# v5_3.net
KiCad netlist of a schematic drawn in EAGLE
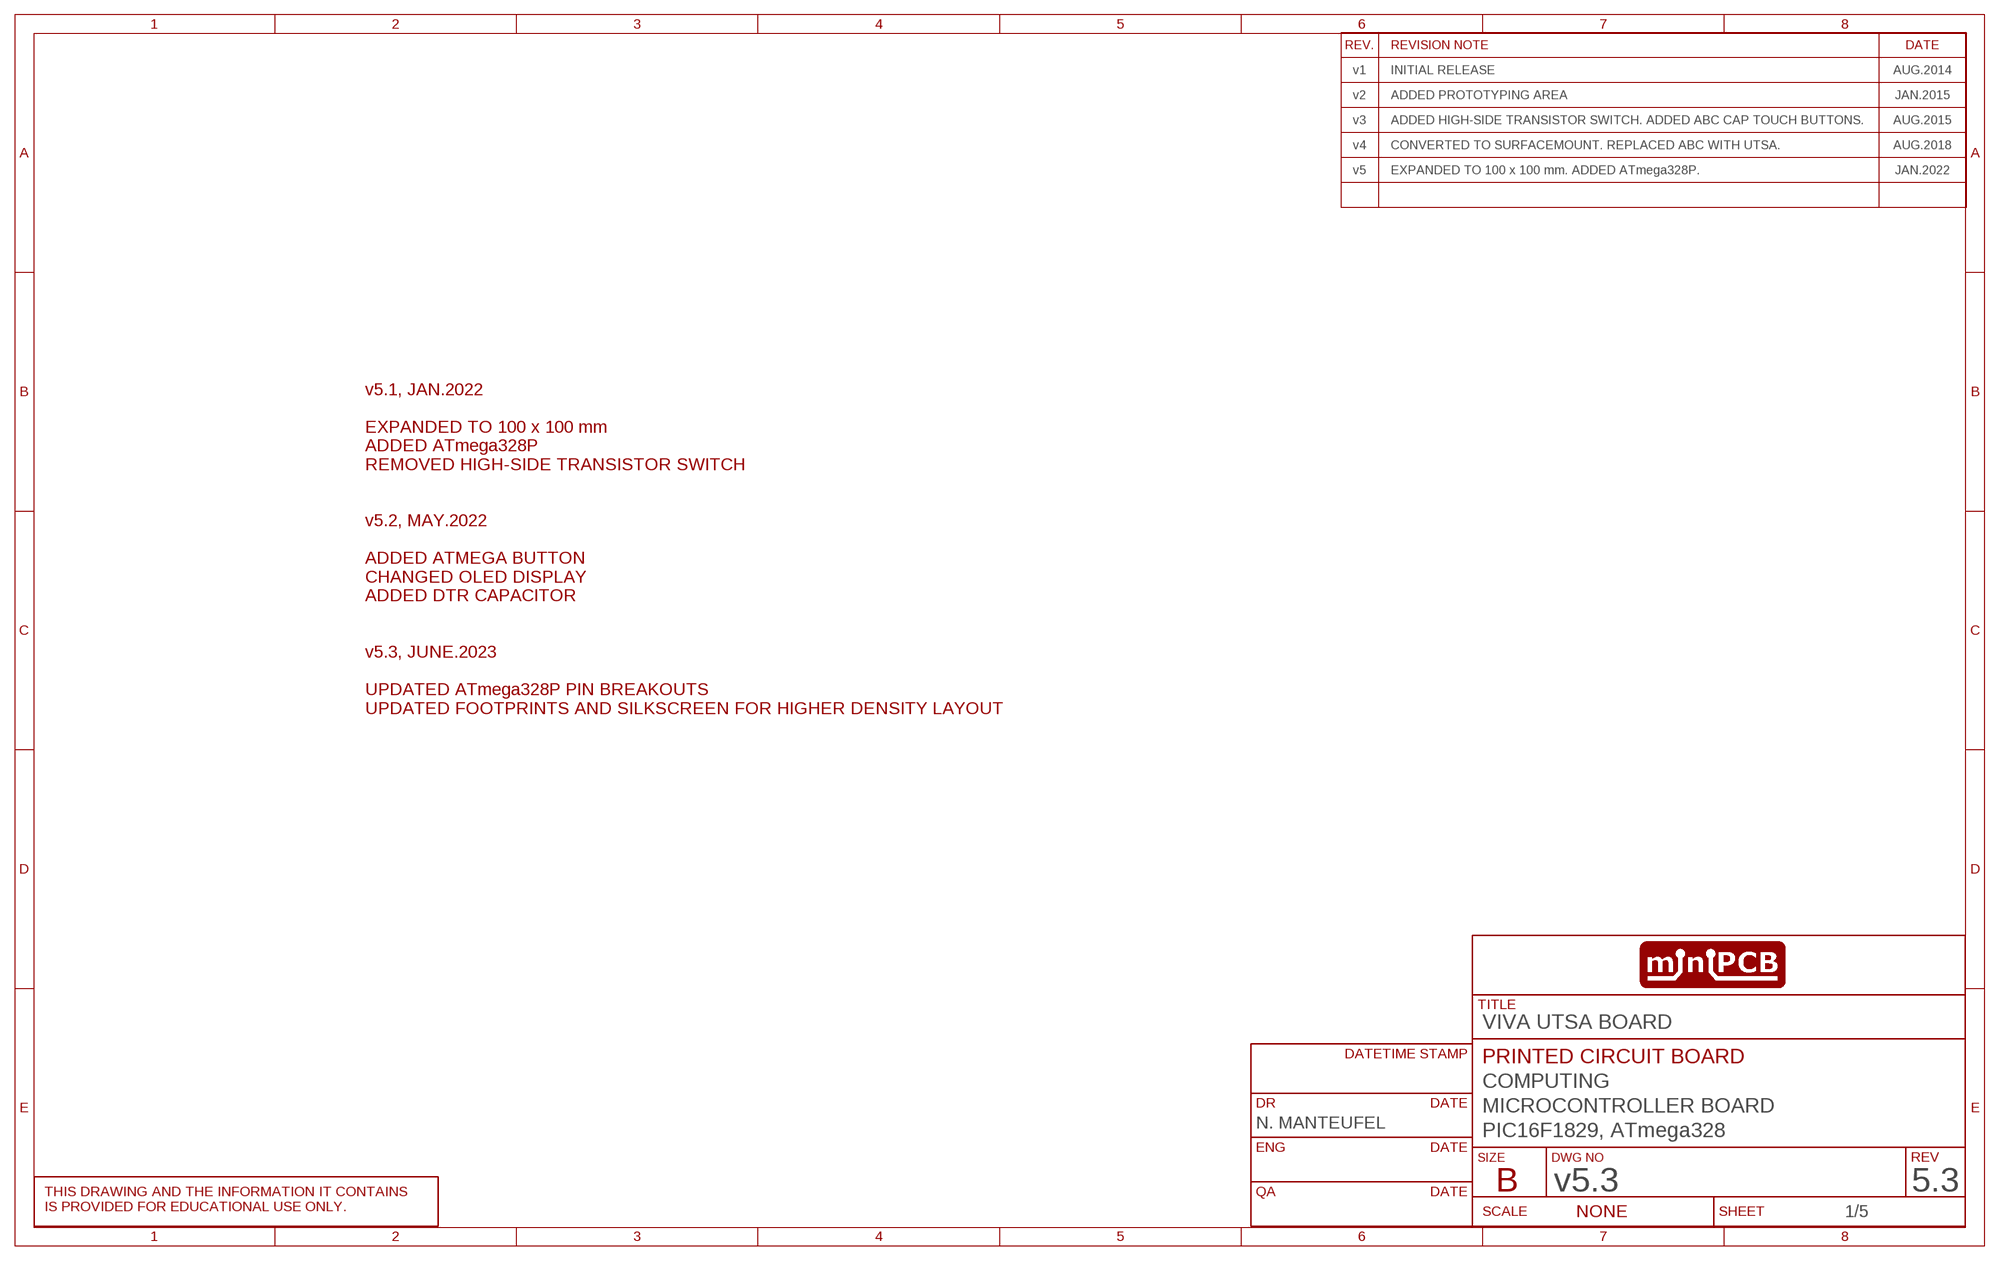
[diagram p0: schematic, sheet 1]
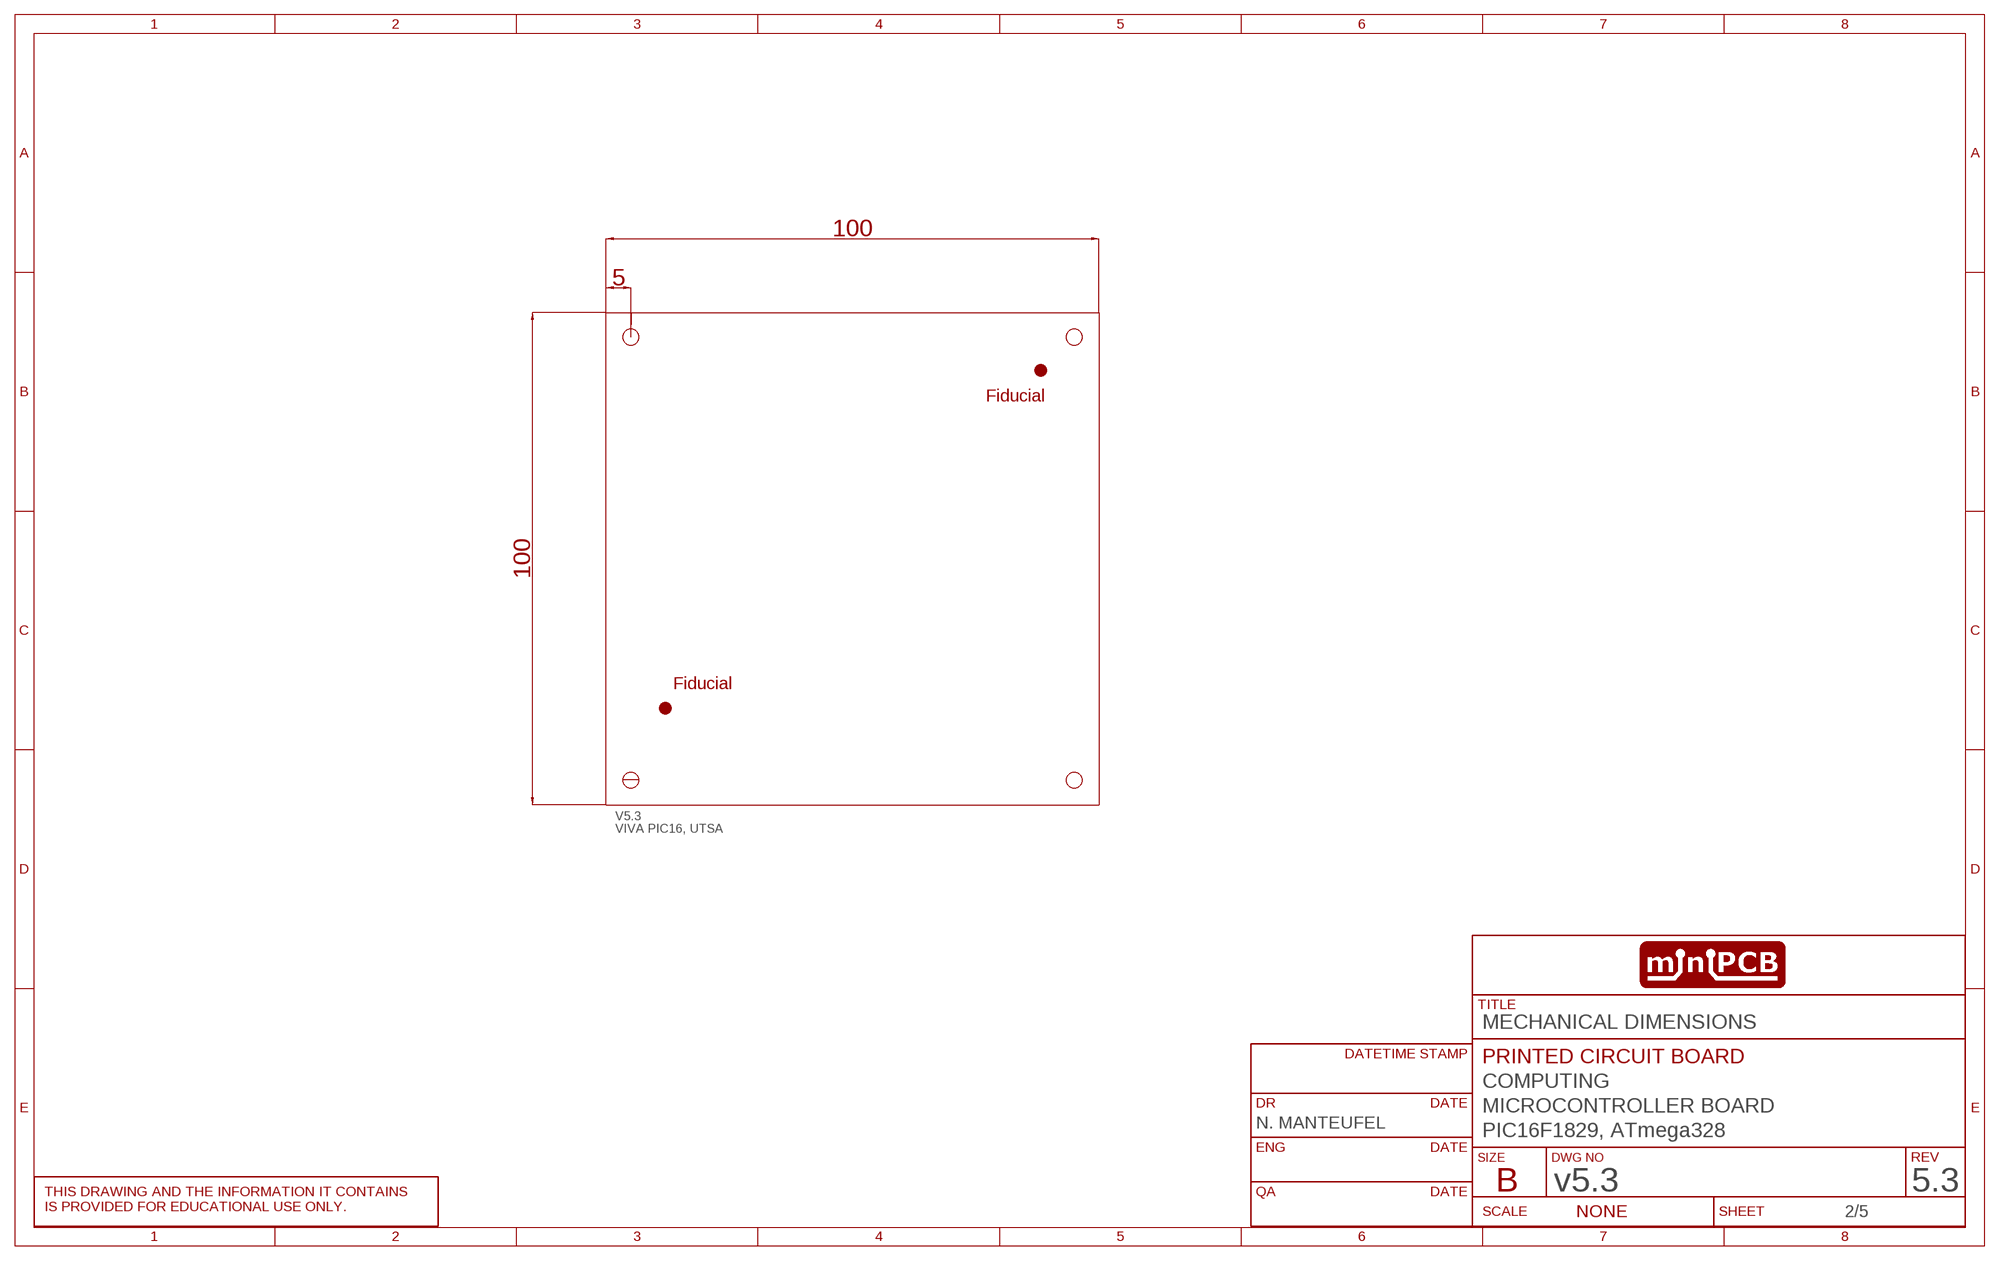
[diagram p1: schematic, sheet 2]
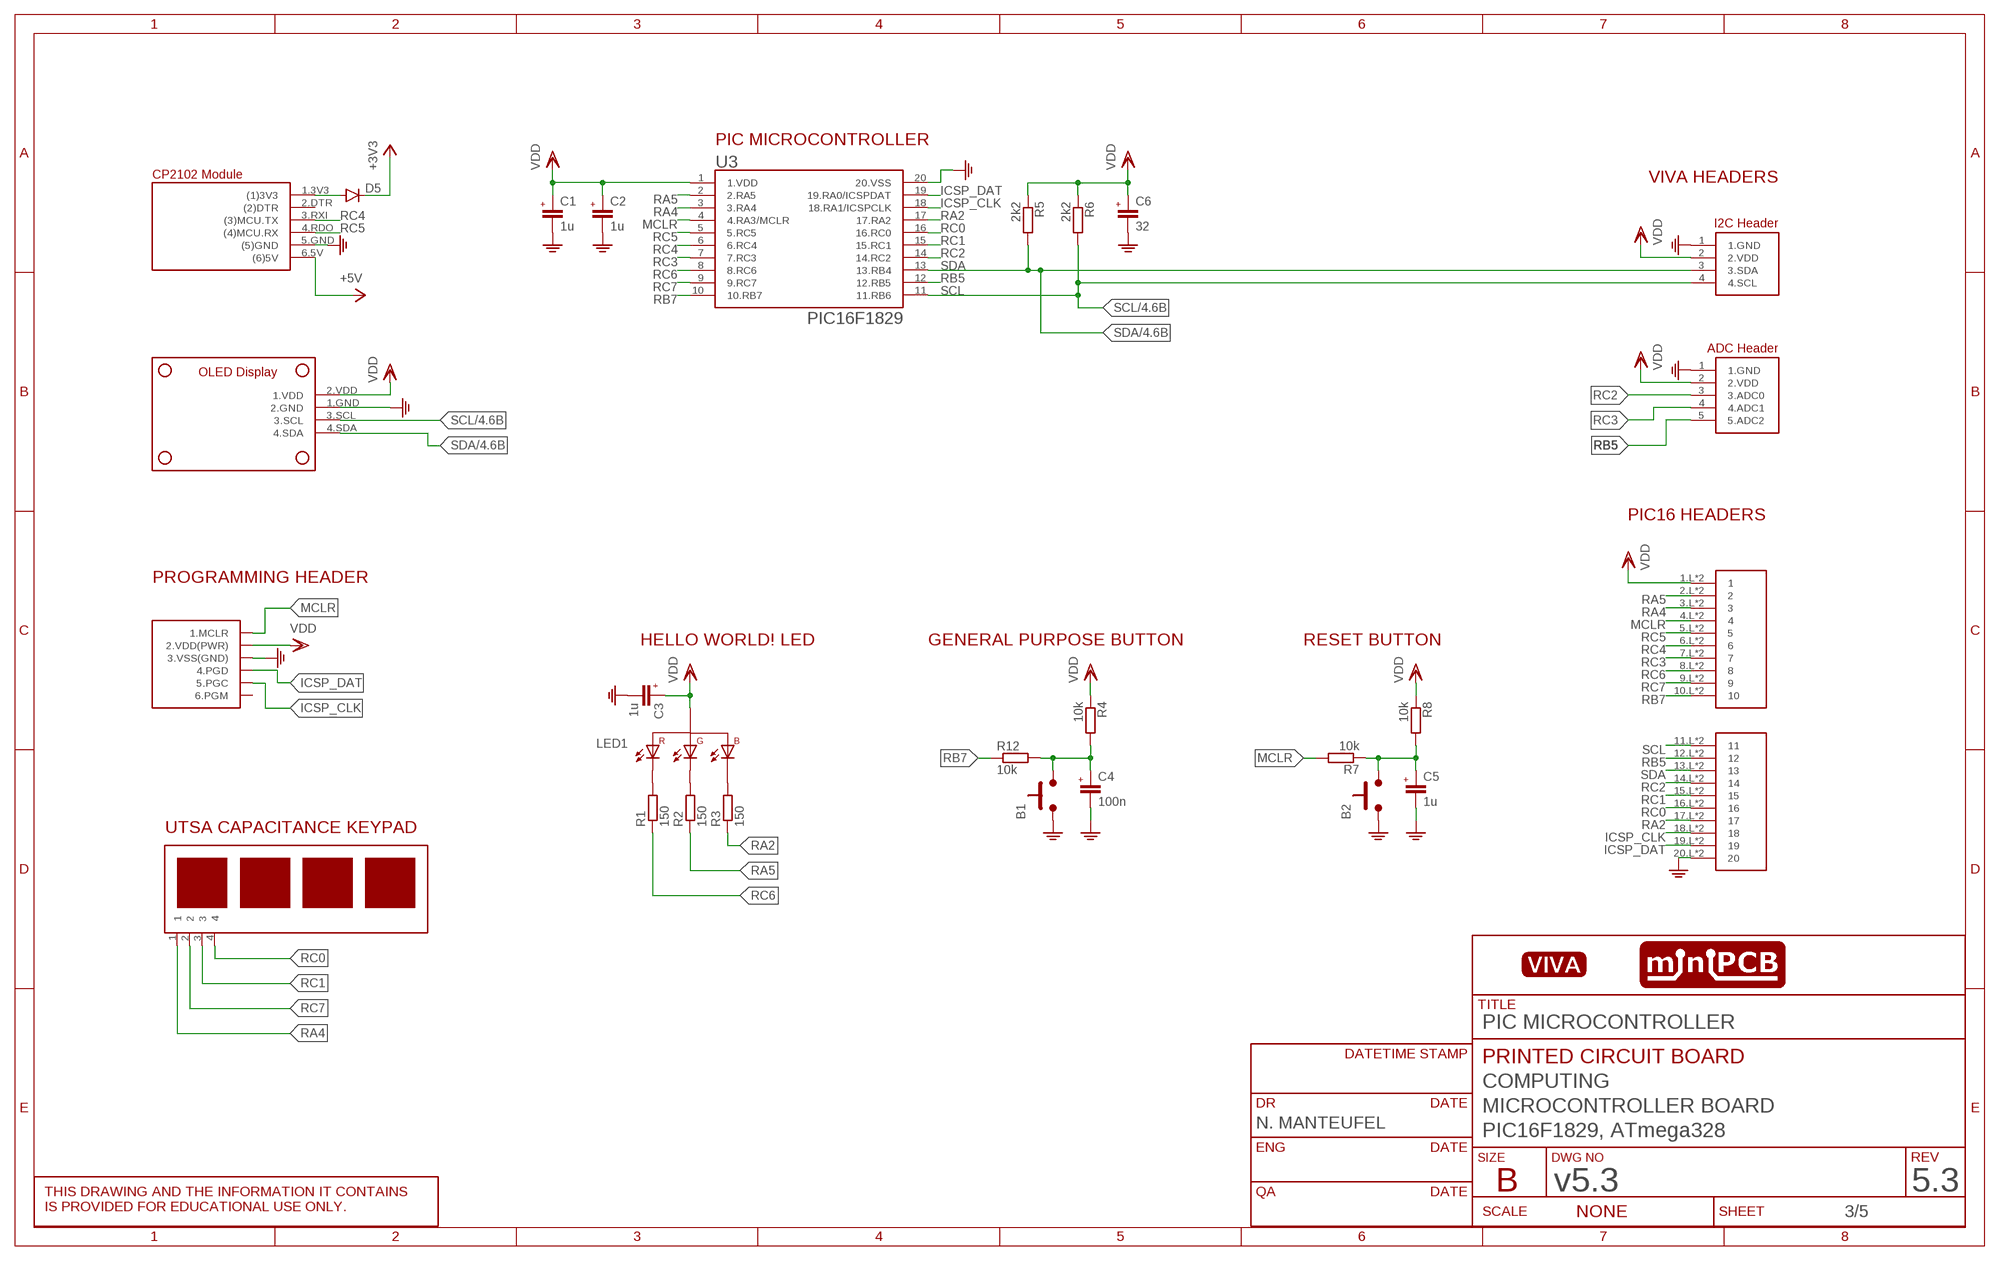
[diagram p2: schematic, sheet 3]
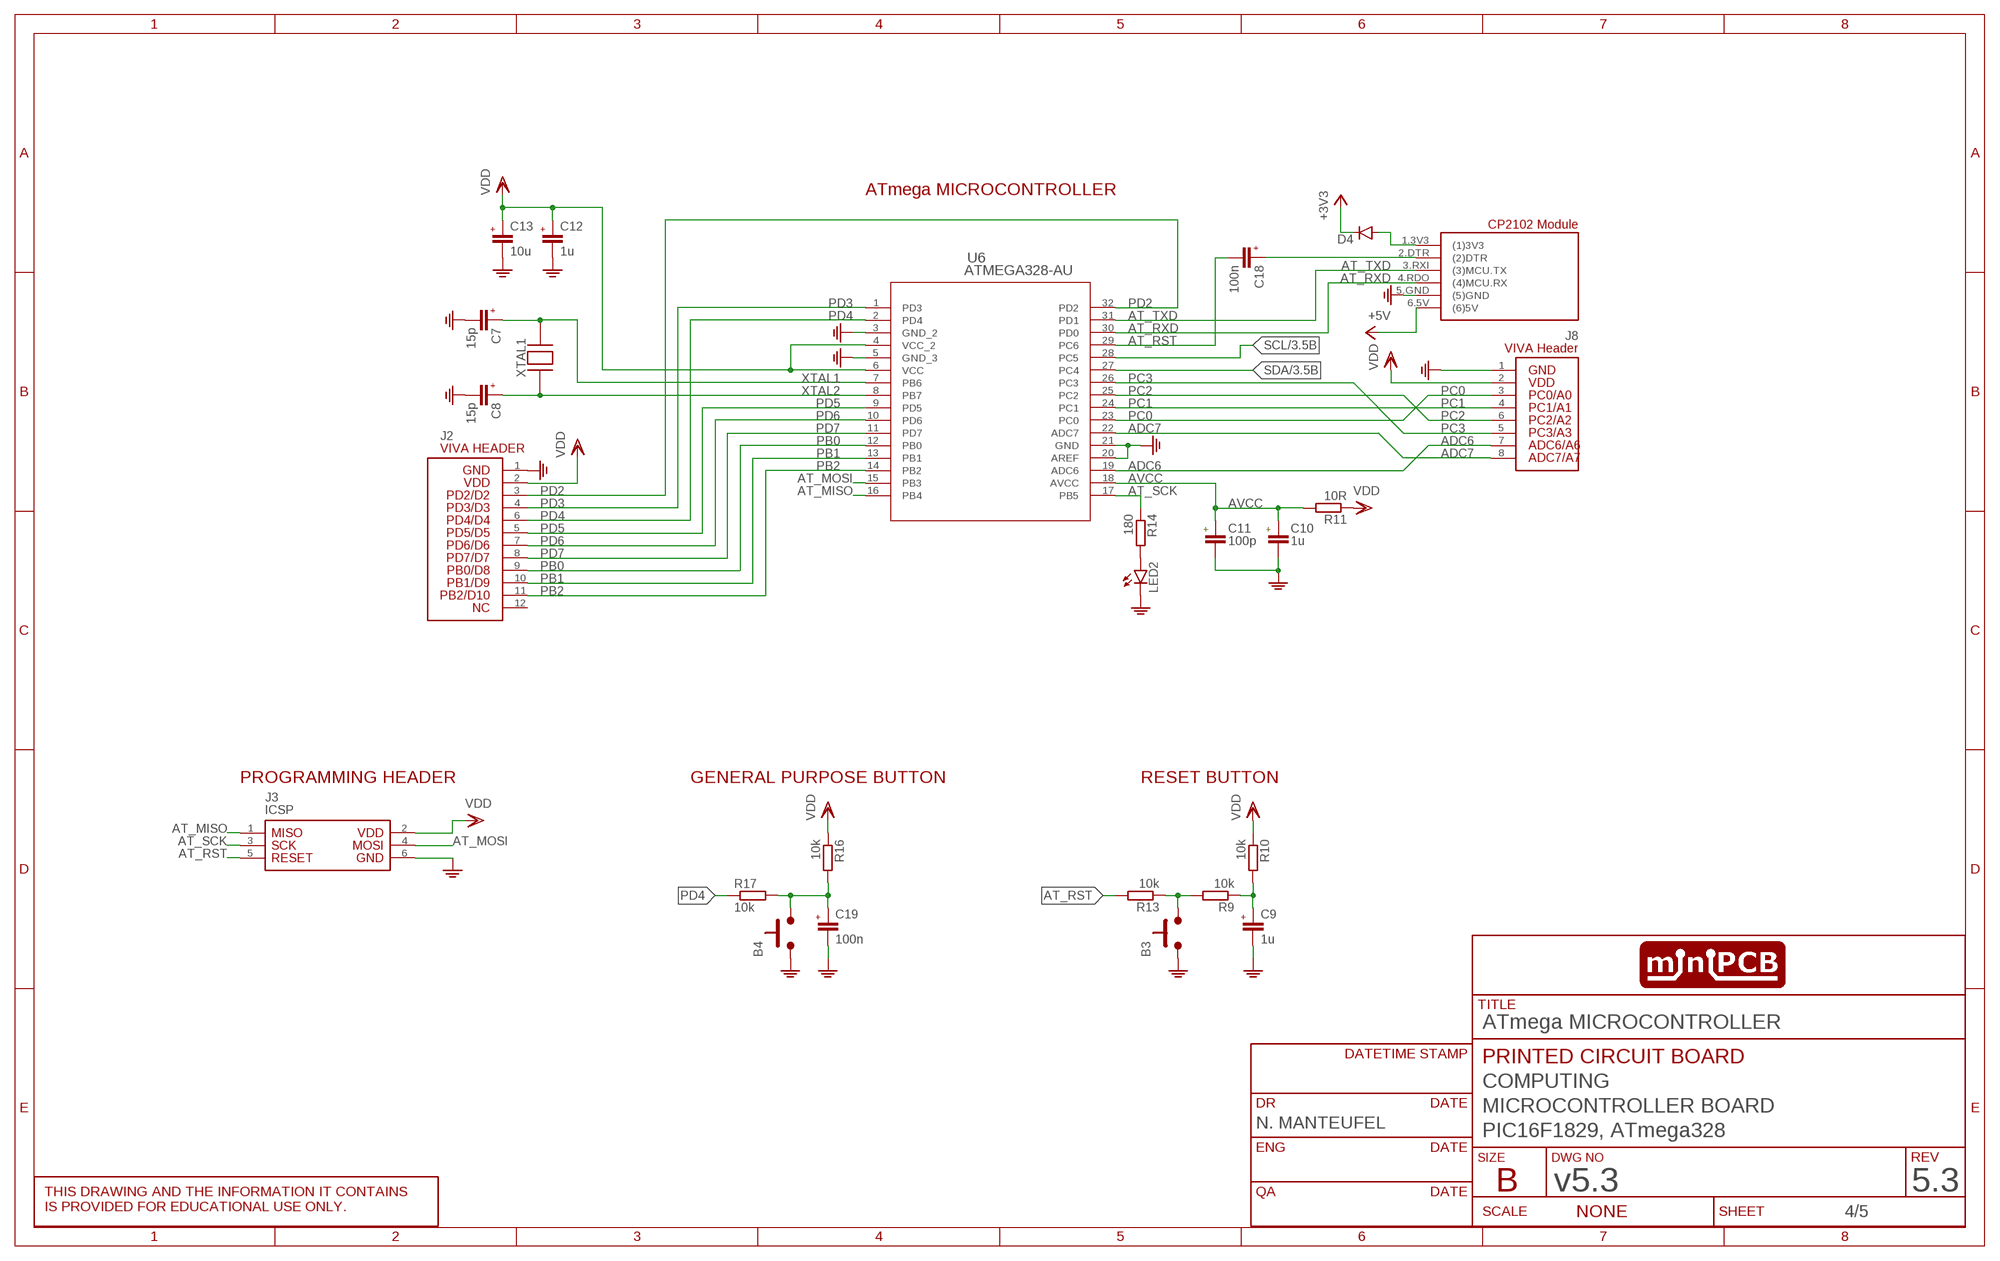
[diagram p3: schematic, sheet 4]
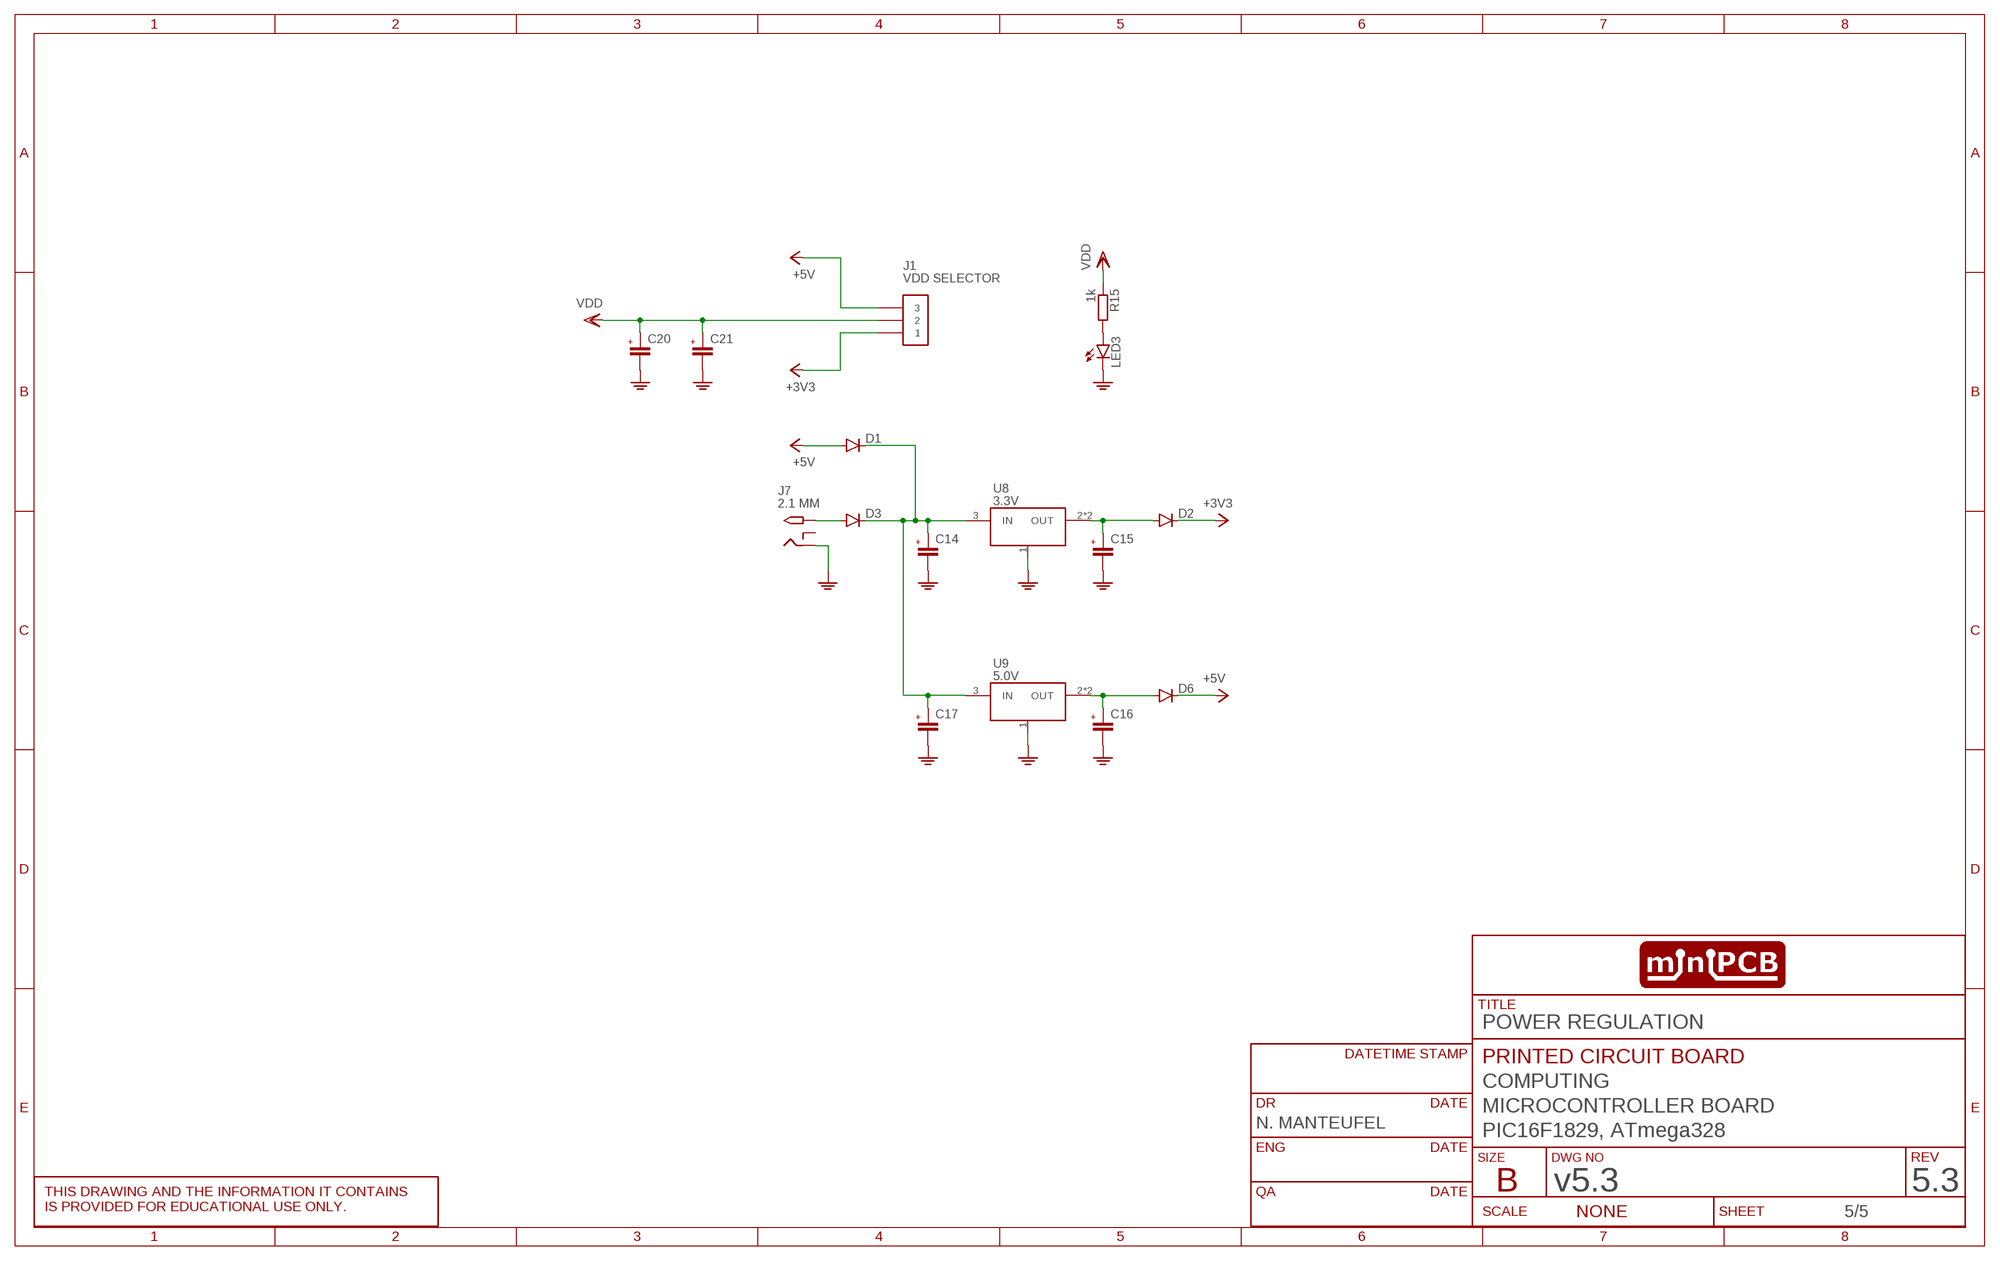
[diagram p4: schematic, sheet 5]

(export (version "E")
  (design (tool "Eeschema 10.0.6"))
  (components
    (comp (ref "A1")
      (value "FIDUCIAL")
      (footprint "eagle-import:FIDUCIAL")
      (libsource (lib "eagle-import") (part "FIDUCIAL"))
    )
    (comp (ref "A2")
      (value "FIDUCIAL")
      (footprint "eagle-import:FIDUCIAL")
      (libsource (lib "eagle-import") (part "FIDUCIAL"))
    )
    (comp (ref "V5.3")
      (value "VIVA PIC16, UTSA")
      (footprint "eagle-import:PCB_100X100")
      (libsource (lib "eagle-import") (part "PCB_100X100"))
    )
    (comp (ref "B3")
      (value "PUSHBUTTON6X6MM")
      (footprint "eagle-import:6X6MM")
      (libsource (lib "eagle-import") (part "PUSHBUTTON6X6MM"))
    )
    (comp (ref "B4")
      (value "PUSHBUTTON6X6MM")
      (footprint "eagle-import:6X6MM")
      (libsource (lib "eagle-import") (part "PUSHBUTTON6X6MM"))
    )
    (comp (ref "C7")
      (value "15p")
      (footprint "eagle-import:C0603")
      (libsource (lib "eagle-import") (part "C0603"))
    )
    (comp (ref "C8")
      (value "15p")
      (footprint "eagle-import:C0603")
      (libsource (lib "eagle-import") (part "C0603"))
    )
    (comp (ref "C9")
      (value "1u")
      (footprint "eagle-import:C0805")
      (libsource (lib "eagle-import") (part "C0805"))
    )
    (comp (ref "C10")
      (value "1u")
      (footprint "eagle-import:C0805")
      (libsource (lib "eagle-import") (part "C-EU_C0805"))
    )
    (comp (ref "C11")
      (value "100p")
      (footprint "eagle-import:C0805")
      (libsource (lib "eagle-import") (part "C-EU_C0805"))
    )
    (comp (ref "C12")
      (value "1u")
      (footprint "eagle-import:C0805")
      (libsource (lib "eagle-import") (part "C0805"))
    )
    (comp (ref "C13")
      (value "10u")
      (footprint "eagle-import:C0805")
      (libsource (lib "eagle-import") (part "C0805"))
    )
    (comp (ref "C18")
      (value "100n")
      (footprint "eagle-import:C0805")
      (libsource (lib "eagle-import") (part "C0805"))
    )
    (comp (ref "C19")
      (value "100n")
      (footprint "eagle-import:C0805")
      (libsource (lib "eagle-import") (part "C0805"))
    )
    (comp (ref "D4")
      (value "DIODE-DO214AC")
      (footprint "eagle-import:DO214AC")
      (libsource (lib "eagle-import") (part "DIODE-DO214AC"))
    )
    (comp (ref "J2")
      (value "VIVA-HEADER-12P")
      (footprint "eagle-import:VIVA-HEADER-12P")
      (fields
        (field (name "P3") "P3 TEXT")
        (field (name "P4") "P4 TEXT")
        (field (name "P5") "P5 TEXT")
        (field (name "P6") "P6 TEXT")
        (field (name "P7") "P7 TEXT")
        (field (name "P8") "P8 TEXT")
        (field (name "P9") "P9 TEXT")
        (field (name "P10") "P10 TEXT")
        (field (name "P11") "P11 TEXT")
        (field (name "P12") "P12 TEXT")
        (field (name "P10_1") "PB1/D9")
        (field (name "P11_1") "PB2/D10")
        (field (name "P12_1") "NC")
        (field (name "P3_1") "PD2/D2")
        (field (name "P4_1") "PD3/D3")
        (field (name "P5_1") "PD4/D4")
        (field (name "P6_1") "PD5/D5")
        (field (name "P7_1") "PD6/D6")
        (field (name "P8_1") "PD7/D7")
        (field (name "P9_1") "PB0/D8")
      )
      (libsource (lib "eagle-import") (part "VIVA-HEADER-12P"))
    )
    (comp (ref "J3")
      (value "ICSP")
      (footprint "eagle-import:PINS_6-2X3_AT")
      (fields
        (field (name "P1") "P1 NAME")
        (field (name "P3") "P3 NAME")
        (field (name "P5") "P5 NAME")
        (field (name "P2") "P2 NAME")
        (field (name "P4") "P4 NAME")
        (field (name "P6") "P6 NAME")
        (field (name "P1_1") "MISO")
        (field (name "P2_1") "VDD")
        (field (name "P3_1") "SCK")
        (field (name "P4_1") "MOSI")
        (field (name "P5_1") "RESET")
        (field (name "P6_1") "GND")
      )
      (libsource (lib "eagle-import") (part "PINS_6-2X3_AT"))
    )
    (comp (ref "J8")
      (value "VIVA-HEADER-ADC-8P")
      (footprint "eagle-import:VIVA-HEADER-ADC-8P")
      (fields
        (field (name "P3") "P3 TEXT")
        (field (name "P4") "P4 TEXT")
        (field (name "P5") "P5 TEXT")
        (field (name "P6") "P6 TEXT")
        (field (name "P7") "P7 TEXT")
        (field (name "P8") "P8 TEXT")
        (field (name "P3_1") "PC0/A0")
        (field (name "P4_1") "PC1/A1")
        (field (name "P5_1") "PC2/A2")
        (field (name "P6_1") "PC3/A3")
        (field (name "P7_1") "ADC6/A6")
        (field (name "P8_1") "ADC7/A7")
      )
      (libsource (lib "eagle-import") (part "VIVA-HEADER-ADC-8P"))
    )
    (comp (ref "LED2")
      (value "LEDSML0805")
      (footprint "eagle-import:SML0805")
      (libsource (lib "eagle-import") (part "LEDSML0805"))
    )
    (comp (ref "R9")
      (value "10k")
      (footprint "eagle-import:R0805")
      (libsource (lib "eagle-import") (part "R-EU__R0805"))
    )
    (comp (ref "R10")
      (value "10k")
      (footprint "eagle-import:R0805")
      (libsource (lib "eagle-import") (part "R-EU__R0805"))
    )
    (comp (ref "R11")
      (value "10R")
      (footprint "eagle-import:R0805")
      (libsource (lib "eagle-import") (part "R-EU__R0805"))
    )
    (comp (ref "R13")
      (value "10k")
      (footprint "eagle-import:R0805")
      (libsource (lib "eagle-import") (part "R-EU__R0805"))
    )
    (comp (ref "R14")
      (value "180")
      (footprint "eagle-import:R0805")
      (libsource (lib "eagle-import") (part "R-EU__R0805"))
    )
    (comp (ref "R16")
      (value "10k")
      (footprint "eagle-import:R0805")
      (libsource (lib "eagle-import") (part "R-EU__R0805"))
    )
    (comp (ref "R17")
      (value "10k")
      (footprint "eagle-import:R0805")
      (libsource (lib "eagle-import") (part "R-EU__R0805"))
    )
    (comp (ref "U6")
      (value "ATMEGA328-AU")
      (footprint "eagle-import:32A_ATM")
      (fields (field (name "COPYRIGHT") "Copyright (C) 2021 Ultra Librarian. All rights reserved."))
      (libsource (lib "eagle-import") (part "ATMEGA328-AU"))
    )
    (comp (ref "U7")
      (value "VIVA_USB-TTL")
      (footprint "eagle-import:VIVA_USB_TTL_SUBTEXT")
      (libsource (lib "eagle-import") (part "VIVA_USB-TTL"))
    )
    (comp (ref "XTAL1")
      (value "CRYSTAL-3225_4P")
      (footprint "eagle-import:TXC7M2")
      (libsource (lib "eagle-import") (part "CRYSTAL-3225_4P"))
    )
    (comp (ref "B1")
      (value "PUSHBUTTON6X6MM")
      (footprint "eagle-import:6X6MM")
      (libsource (lib "eagle-import") (part "PUSHBUTTON6X6MM"))
    )
    (comp (ref "B2")
      (value "PUSHBUTTON6X6MM")
      (footprint "eagle-import:6X6MM")
      (libsource (lib "eagle-import") (part "PUSHBUTTON6X6MM"))
    )
    (comp (ref "C1")
      (value "1u")
      (footprint "eagle-import:C0805")
      (libsource (lib "eagle-import") (part "C0805"))
    )
    (comp (ref "C2")
      (value "1u")
      (footprint "eagle-import:C0805")
      (libsource (lib "eagle-import") (part "C0805"))
    )
    (comp (ref "C3")
      (value "1u")
      (footprint "eagle-import:C0805")
      (libsource (lib "eagle-import") (part "C0805"))
    )
    (comp (ref "C4")
      (value "100n")
      (footprint "eagle-import:C0805")
      (libsource (lib "eagle-import") (part "C0805"))
    )
    (comp (ref "C5")
      (value "1u")
      (footprint "eagle-import:C0805")
      (libsource (lib "eagle-import") (part "C0805"))
    )
    (comp (ref "C6")
      (value "32")
      (footprint "eagle-import:C0805")
      (libsource (lib "eagle-import") (part "C0805"))
    )
    (comp (ref "D5")
      (value "DIODE-DO214AC")
      (footprint "eagle-import:DO214AC")
      (libsource (lib "eagle-import") (part "DIODE-DO214AC"))
    )
    (comp (ref "J4")
      (value "PICKIT3")
      (footprint "eagle-import:PICKIT3")
      (libsource (lib "eagle-import") (part "PICKIT3"))
    )
    (comp (ref "J5")
      (value "VIVA-HEADER-ADC-PIC16")
      (footprint "eagle-import:VIVA-HEADER-ADC-PIC16")
      (libsource (lib "eagle-import") (part "VIVA-HEADER-ADC-PIC16"))
    )
    (comp (ref "LED1")
      (value "LED_RGBLTST-C19FD1WT")
      (footprint "eagle-import:0805_RGB")
      (libsource (lib "eagle-import") (part "LED_RGBLTST-C19FD1WT"))
    )
    (comp (ref "R1")
      (value "150")
      (footprint "eagle-import:R0805")
      (libsource (lib "eagle-import") (part "R-EU__R0805"))
    )
    (comp (ref "R2")
      (value "150")
      (footprint "eagle-import:R0805")
      (libsource (lib "eagle-import") (part "R-EU__R0805"))
    )
    (comp (ref "R3")
      (value "150")
      (footprint "eagle-import:R0805")
      (libsource (lib "eagle-import") (part "R-EU__R0805"))
    )
    (comp (ref "R4")
      (value "10k")
      (footprint "eagle-import:R0805")
      (libsource (lib "eagle-import") (part "R-EU__R0805"))
    )
    (comp (ref "R5")
      (value "2k2")
      (footprint "eagle-import:R0805")
      (libsource (lib "eagle-import") (part "R-EU__R0805"))
    )
    (comp (ref "R6")
      (value "2k2")
      (footprint "eagle-import:R0805")
      (libsource (lib "eagle-import") (part "R-EU__R0805"))
    )
    (comp (ref "R7")
      (value "10k")
      (footprint "eagle-import:R0805")
      (libsource (lib "eagle-import") (part "R-EU__R0805"))
    )
    (comp (ref "R8")
      (value "10k")
      (footprint "eagle-import:R0805")
      (libsource (lib "eagle-import") (part "R-EU__R0805"))
    )
    (comp (ref "R12")
      (value "10k")
      (footprint "eagle-import:R0805")
      (libsource (lib "eagle-import") (part "R-EU__R0805"))
    )
    (comp (ref "U$2")
      (value "VIVA_LOGO")
      (footprint "eagle-import:VIVA_LOGO")
      (libsource (lib "eagle-import") (part "VIVA_LOGO"))
    )
    (comp (ref "U$3")
      (value "VIVA_OLEDGND")
      (footprint "eagle-import:VIVA_OLED-I2C-ALT")
      (libsource (lib "eagle-import") (part "VIVA_OLEDGND"))
    )
    (comp (ref "U1")
      (value "VIVA_UTSA-KEYPADV5")
      (footprint "eagle-import:VIVA_UTSA-KEYPAD-V5")
      (libsource (lib "eagle-import") (part "VIVA_UTSA-KEYPADV5"))
    )
    (comp (ref "U2")
      (value "VIVA_USB-TTL")
      (footprint "eagle-import:VIVA_USB_TTL_SUBTEXT")
      (libsource (lib "eagle-import") (part "VIVA_USB-TTL"))
    )
    (comp (ref "U3")
      (value "PIC16F1829")
      (footprint "eagle-import:SOP20-NEW")
      (libsource (lib "eagle-import") (part "PIC16F1829300"))
    )
    (comp (ref "U4")
      (value "VIVA-HEADER-I2C-RA")
      (footprint "eagle-import:VIVA-HEADER-I2C-RA")
      (libsource (lib "eagle-import") (part "VIVA-HEADER-I2C-RA"))
    )
    (comp (ref "U5")
      (value "VIVA_PIC16BOARD")
      (footprint "eagle-import:VIVA_PIC16")
      (libsource (lib "eagle-import") (part "VIVA_PIC16BOARD"))
    )
    (comp (ref "C14")
      (value "C0805")
      (footprint "eagle-import:C0805")
      (libsource (lib "eagle-import") (part "C0805"))
    )
    (comp (ref "C15")
      (value "C0805")
      (footprint "eagle-import:C0805")
      (libsource (lib "eagle-import") (part "C0805"))
    )
    (comp (ref "C16")
      (value "C0805")
      (footprint "eagle-import:C0805")
      (libsource (lib "eagle-import") (part "C0805"))
    )
    (comp (ref "C17")
      (value "C0805")
      (footprint "eagle-import:C0805")
      (libsource (lib "eagle-import") (part "C0805"))
    )
    (comp (ref "C20")
      (value "C0805")
      (footprint "eagle-import:C0805")
      (libsource (lib "eagle-import") (part "C0805"))
    )
    (comp (ref "C21")
      (value "C0805")
      (footprint "eagle-import:C0805")
      (libsource (lib "eagle-import") (part "C0805"))
    )
    (comp (ref "D1")
      (value "DIODE-DO214AC")
      (footprint "eagle-import:DO214AC")
      (libsource (lib "eagle-import") (part "DIODE-DO214AC"))
    )
    (comp (ref "D2")
      (value "DIODE-DO214AC")
      (footprint "eagle-import:DO214AC")
      (libsource (lib "eagle-import") (part "DIODE-DO214AC"))
    )
    (comp (ref "D3")
      (value "DIODE-DO214AC")
      (footprint "eagle-import:DO214AC")
      (libsource (lib "eagle-import") (part "DIODE-DO214AC"))
    )
    (comp (ref "D6")
      (value "DIODE-DO214AC")
      (footprint "eagle-import:DO214AC")
      (libsource (lib "eagle-import") (part "DIODE-DO214AC"))
    )
    (comp (ref "J1")
      (value "VDD SELECTOR")
      (footprint "eagle-import:PINS_3")
      (libsource (lib "eagle-import") (part "PINS_3_2.54"))
    )
    (comp (ref "J7")
      (value "2.1 MM")
      (footprint "eagle-import:PJ-102A")
      (libsource (lib "eagle-import") (part "2.1MMJACKTHM"))
    )
    (comp (ref "LED3")
      (value "LEDSML0805")
      (footprint "eagle-import:SML0805")
      (libsource (lib "eagle-import") (part "LEDSML0805"))
    )
    (comp (ref "R15")
      (value "1k")
      (footprint "eagle-import:R0805")
      (libsource (lib "eagle-import") (part "R-EU__R0805"))
    )
    (comp (ref "U8")
      (value "3.3V")
      (footprint "eagle-import:SOT223")
      (libsource (lib "eagle-import") (part "REGULATOR_SCHLM1117"))
    )
    (comp (ref "U9")
      (value "5.0V")
      (footprint "eagle-import:SOT223")
      (libsource (lib "eagle-import") (part "REGULATOR_SCHLM1117"))
    )
  )
  (nets
    (net (code "1") (name "+3V3") (class "Default")
      (node (ref "D2") (pin "C") (pinfunction "C_C") (pintype "passive"))
      (node (ref "D4") (pin "C") (pinfunction "C_C") (pintype "passive"))
      (node (ref "D5") (pin "C") (pinfunction "C_C") (pintype "passive"))
      (node (ref "J1") (pin "1") (pinfunction "1_1") (pintype "bidirectional"))
    )
    (net (code "2") (name "+5V") (class "Default")
      (node (ref "D1") (pin "A") (pinfunction "A_A") (pintype "passive"))
      (node (ref "D6") (pin "C") (pinfunction "C_C") (pintype "passive"))
      (node (ref "J1") (pin "3") (pinfunction "3_3") (pintype "bidirectional"))
      (node (ref "U2") (pin "6.5V") (pinfunction "(6)5V_6.5V") (pintype "bidirectional"))
      (node (ref "U7") (pin "6.5V") (pinfunction "(6)5V_6.5V") (pintype "bidirectional"))
    )
    (net (code "3") (name "ADC6") (class "Default")
      (node (ref "J8") (pin "7") (pinfunction "5.ADC3_7") (pintype "bidirectional"))
      (node (ref "U6") (pin "19") (pinfunction "ADC6_19") (pintype "passive"))
    )
    (net (code "4") (name "ADC7") (class "Default")
      (node (ref "J8") (pin "8") (pinfunction "5.ADC4_8") (pintype "bidirectional"))
      (node (ref "U6") (pin "22") (pinfunction "ADC7_22") (pintype "passive"))
    )
    (net (code "5") (name "AT_MISO") (class "Default")
      (node (ref "J3") (pin "1") (pinfunction "1_1") (pintype "bidirectional"))
      (node (ref "U6") (pin "16") (pinfunction "PB4_16") (pintype "bidirectional"))
    )
    (net (code "6") (name "AT_MOSI") (class "Default")
      (node (ref "J3") (pin "4") (pinfunction "4_4") (pintype "bidirectional"))
      (node (ref "U6") (pin "15") (pinfunction "PB3_15") (pintype "bidirectional"))
    )
    (net (code "7") (name "AT_RST") (class "Default")
      (node (ref "C18") (pin "2") (pinfunction "-_2") (pintype "passive"))
      (node (ref "J3") (pin "5") (pinfunction "5_5") (pintype "bidirectional"))
      (node (ref "R13") (pin "2") (pinfunction "2_2") (pintype "passive"))
      (node (ref "U6") (pin "29") (pinfunction "PC6_29") (pintype "bidirectional"))
    )
    (net (code "8") (name "AT_RXD") (class "Default")
      (node (ref "U6") (pin "30") (pinfunction "PD0_30") (pintype "bidirectional"))
      (node (ref "U7") (pin "4.RDO") (pinfunction "(4)MCU.RX_4.RDO") (pintype "bidirectional"))
    )
    (net (code "9") (name "AT_SCK") (class "Default")
      (node (ref "J3") (pin "3") (pinfunction "3_3") (pintype "bidirectional"))
      (node (ref "R14") (pin "1") (pinfunction "1_1") (pintype "passive"))
      (node (ref "U6") (pin "17") (pinfunction "PB5_17") (pintype "bidirectional"))
    )
    (net (code "10") (name "AT_TXD") (class "Default")
      (node (ref "U6") (pin "31") (pinfunction "PD1_31") (pintype "bidirectional"))
      (node (ref "U7") (pin "3.RXI") (pinfunction "(3)MCU.TX_3.RXI") (pintype "bidirectional"))
    )
    (net (code "11") (name "AVCC") (class "Default")
      (node (ref "C10") (pin "1") (pinfunction "1_1") (pintype "passive"))
      (node (ref "C11") (pin "1") (pinfunction "1_1") (pintype "passive"))
      (node (ref "R11") (pin "2") (pinfunction "2_2") (pintype "passive"))
      (node (ref "U6") (pin "18") (pinfunction "AVCC_18") (pintype "power_in"))
    )
    (net (code "12") (name "GND") (class "Default")
      (node (ref "B1") (pin "1.A") (pinfunction "1_1.A") (pintype "bidirectional"))
      (node (ref "B1") (pin "2.A") (pinfunction "1_2.A") (pintype "bidirectional"))
      (node (ref "B2") (pin "1.A") (pinfunction "1_1.A") (pintype "bidirectional"))
      (node (ref "B2") (pin "2.A") (pinfunction "1_2.A") (pintype "bidirectional"))
      (node (ref "B3") (pin "1.A") (pinfunction "1_1.A") (pintype "bidirectional"))
      (node (ref "B3") (pin "2.A") (pinfunction "1_2.A") (pintype "bidirectional"))
      (node (ref "B4") (pin "1.A") (pinfunction "1_1.A") (pintype "bidirectional"))
      (node (ref "B4") (pin "2.A") (pinfunction "1_2.A") (pintype "bidirectional"))
      (node (ref "C1") (pin "2") (pinfunction "-_2") (pintype "passive"))
      (node (ref "C10") (pin "2") (pinfunction "2_2") (pintype "passive"))
      (node (ref "C11") (pin "2") (pinfunction "2_2") (pintype "passive"))
      (node (ref "C12") (pin "2") (pinfunction "-_2") (pintype "passive"))
      (node (ref "C13") (pin "2") (pinfunction "-_2") (pintype "passive"))
      (node (ref "C14") (pin "2") (pinfunction "-_2") (pintype "passive"))
      (node (ref "C15") (pin "2") (pinfunction "-_2") (pintype "passive"))
      (node (ref "C16") (pin "2") (pinfunction "-_2") (pintype "passive"))
      (node (ref "C17") (pin "2") (pinfunction "-_2") (pintype "passive"))
      (node (ref "C19") (pin "2") (pinfunction "-_2") (pintype "passive"))
      (node (ref "C2") (pin "2") (pinfunction "-_2") (pintype "passive"))
      (node (ref "C20") (pin "2") (pinfunction "-_2") (pintype "passive"))
      (node (ref "C21") (pin "2") (pinfunction "-_2") (pintype "passive"))
      (node (ref "C3") (pin "2") (pinfunction "-_2") (pintype "passive"))
      (node (ref "C4") (pin "2") (pinfunction "-_2") (pintype "passive"))
      (node (ref "C5") (pin "2") (pinfunction "-_2") (pintype "passive"))
      (node (ref "C6") (pin "2") (pinfunction "-_2") (pintype "passive"))
      (node (ref "C7") (pin "1") (pinfunction "-_1") (pintype "passive"))
      (node (ref "C8") (pin "1") (pinfunction "-_1") (pintype "passive"))
      (node (ref "C9") (pin "2") (pinfunction "-_2") (pintype "passive"))
      (node (ref "J2") (pin "1") (pinfunction "1.GND_1") (pintype "bidirectional"))
      (node (ref "J3") (pin "6") (pinfunction "6_6") (pintype "bidirectional"))
      (node (ref "J4") (pin "3") (pinfunction "3.VSS(GND)_3") (pintype "bidirectional"))
      (node (ref "J5") (pin "1") (pinfunction "1.GND_1") (pintype "bidirectional"))
      (node (ref "J7") (pin "RING") (pinfunction "RING_RING") (pintype "bidirectional"))
      (node (ref "J8") (pin "1") (pinfunction "1.GND_1") (pintype "bidirectional"))
      (node (ref "LED2") (pin "C") (pinfunction "C_C") (pintype "passive"))
      (node (ref "LED3") (pin "C") (pinfunction "C_C") (pintype "passive"))
      (node (ref "U$3") (pin "1.GND") (pinfunction "2.GND_1.GND") (pintype "bidirectional"))
      (node (ref "U2") (pin "5.GND") (pinfunction "(5)GND_5.GND") (pintype "bidirectional"))
      (node (ref "U3") (pin "20") (pinfunction "20.VSS_20") (pintype "bidirectional"))
      (node (ref "U4") (pin "1") (pinfunction "1.GND_1") (pintype "bidirectional"))
      (node (ref "U5") (pin "20.L") (pinfunction "20_20.L") (pintype "bidirectional"))
      (node (ref "U5") (pin "20.R") (pinfunction "20_20.R") (pintype "bidirectional"))
      (node (ref "U6") (pin "20") (pinfunction "AREF_20") (pintype "passive"))
      (node (ref "U6") (pin "21") (pinfunction "GND_21") (pintype "power_in"))
      (node (ref "U6") (pin "3") (pinfunction "GND_2_3") (pintype "power_in"))
      (node (ref "U6") (pin "5") (pinfunction "GND_3_5") (pintype "power_in"))
      (node (ref "U7") (pin "5.GND") (pinfunction "(5)GND_5.GND") (pintype "bidirectional"))
      (node (ref "U8") (pin "1") (pinfunction "GND_1") (pintype "bidirectional"))
      (node (ref "U9") (pin "1") (pinfunction "GND_1") (pintype "bidirectional"))
    )
    (net (code "13") (name "ICSP_CLK") (class "Default")
      (node (ref "J4") (pin "5") (pinfunction "5.PGC_5") (pintype "bidirectional"))
      (node (ref "U3") (pin "18") (pinfunction "18.RA1/ICSPCLK_18") (pintype "bidirectional"))
      (node (ref "U5") (pin "18.L") (pinfunction "18_18.L") (pintype "bidirectional"))
      (node (ref "U5") (pin "18.R") (pinfunction "18_18.R") (pintype "bidirectional"))
    )
    (net (code "14") (name "ICSP_DAT") (class "Default")
      (node (ref "J4") (pin "4") (pinfunction "4.PGD_4") (pintype "bidirectional"))
      (node (ref "U3") (pin "19") (pinfunction "19.RA0/ICSPDAT_19") (pintype "bidirectional"))
      (node (ref "U5") (pin "19.L") (pinfunction "19_19.L") (pintype "bidirectional"))
      (node (ref "U5") (pin "19.R") (pinfunction "19_19.R") (pintype "bidirectional"))
    )
    (net (code "15") (name "MCLR") (class "Default")
      (node (ref "J4") (pin "1") (pinfunction "1.MCLR_1") (pintype "bidirectional"))
      (node (ref "R7") (pin "2") (pinfunction "2_2") (pintype "passive"))
      (node (ref "U3") (pin "4") (pinfunction "4.RA3/MCLR_4") (pintype "bidirectional"))
      (node (ref "U5") (pin "4.L") (pinfunction "4_4.L") (pintype "bidirectional"))
      (node (ref "U5") (pin "4.R") (pinfunction "4_4.R") (pintype "bidirectional"))
    )
    (net (code "16") (name "Net-(B3-2-Pad3.B)") (class "Default")
      (node (ref "B3") (pin "3.B") (pinfunction "2_3.B") (pintype "bidirectional"))
      (node (ref "B3") (pin "4.B") (pinfunction "2_4.B") (pintype "bidirectional"))
      (node (ref "R13") (pin "1") (pinfunction "1_1") (pintype "passive"))
      (node (ref "R9") (pin "2") (pinfunction "2_2") (pintype "passive"))
    )
    (net (code "17") (name "Net-(C4-+)") (class "Default")
      (node (ref "B1") (pin "3.B") (pinfunction "2_3.B") (pintype "bidirectional"))
      (node (ref "B1") (pin "4.B") (pinfunction "2_4.B") (pintype "bidirectional"))
      (node (ref "C4") (pin "1") (pinfunction "+_1") (pintype "passive"))
      (node (ref "R12") (pin "2") (pinfunction "2_2") (pintype "passive"))
      (node (ref "R4") (pin "2") (pinfunction "2_2") (pintype "passive"))
    )
    (net (code "18") (name "Net-(C5-+)") (class "Default")
      (node (ref "B2") (pin "3.B") (pinfunction "2_3.B") (pintype "bidirectional"))
      (node (ref "B2") (pin "4.B") (pinfunction "2_4.B") (pintype "bidirectional"))
      (node (ref "C5") (pin "1") (pinfunction "+_1") (pintype "passive"))
      (node (ref "R7") (pin "1") (pinfunction "1_1") (pintype "passive"))
      (node (ref "R8") (pin "2") (pinfunction "2_2") (pintype "passive"))
    )
    (net (code "19") (name "Net-(C9-+)") (class "Default")
      (node (ref "C9") (pin "1") (pinfunction "+_1") (pintype "passive"))
      (node (ref "R10") (pin "2") (pinfunction "2_2") (pintype "passive"))
      (node (ref "R9") (pin "1") (pinfunction "1_1") (pintype "passive"))
    )
    (net (code "20") (name "Net-(C14-+)") (class "Default")
      (node (ref "C14") (pin "1") (pinfunction "+_1") (pintype "passive"))
      (node (ref "C17") (pin "1") (pinfunction "+_1") (pintype "passive"))
      (node (ref "D1") (pin "C") (pinfunction "C_C") (pintype "passive"))
      (node (ref "D3") (pin "C") (pinfunction "C_C") (pintype "passive"))
      (node (ref "U8") (pin "3") (pinfunction "IN_3") (pintype "bidirectional"))
      (node (ref "U9") (pin "3") (pinfunction "IN_3") (pintype "bidirectional"))
    )
    (net (code "21") (name "Net-(C15-+)") (class "Default")
      (node (ref "C15") (pin "1") (pinfunction "+_1") (pintype "passive"))
      (node (ref "D2") (pin "A") (pinfunction "A_A") (pintype "passive"))
      (node (ref "U8") (pin "2") (pinfunction "OUT_2") (pintype "bidirectional"))
      (node (ref "U8") (pin "4.TAB") (pinfunction "OUT_4.TAB") (pintype "bidirectional"))
    )
    (net (code "22") (name "Net-(C16-+)") (class "Default")
      (node (ref "C16") (pin "1") (pinfunction "+_1") (pintype "passive"))
      (node (ref "D6") (pin "A") (pinfunction "A_A") (pintype "passive"))
      (node (ref "U9") (pin "2") (pinfunction "OUT_2") (pintype "bidirectional"))
      (node (ref "U9") (pin "4.TAB") (pinfunction "OUT_4.TAB") (pintype "bidirectional"))
    )
    (net (code "23") (name "Net-(C18-+)") (class "Default")
      (node (ref "C18") (pin "1") (pinfunction "+_1") (pintype "passive"))
      (node (ref "U7") (pin "2.DTR") (pinfunction "(2)DTR_2.DTR") (pintype "bidirectional"))
    )
    (net (code "24") (name "Net-(C19-+)") (class "Default")
      (node (ref "B4") (pin "3.B") (pinfunction "2_3.B") (pintype "bidirectional"))
      (node (ref "B4") (pin "4.B") (pinfunction "2_4.B") (pintype "bidirectional"))
      (node (ref "C19") (pin "1") (pinfunction "+_1") (pintype "passive"))
      (node (ref "R16") (pin "2") (pinfunction "2_2") (pintype "passive"))
      (node (ref "R17") (pin "2") (pinfunction "2_2") (pintype "passive"))
    )
    (net (code "25") (name "Net-(D3-PadA)") (class "Default")
      (node (ref "D3") (pin "A") (pinfunction "A_A") (pintype "passive"))
      (node (ref "J7") (pin "TIP") (pinfunction "TIP_TIP") (pintype "bidirectional"))
    )
    (net (code "26") (name "Net-(LED1-1.R-)") (class "Default")
      (node (ref "LED1") (pin "2") (pinfunction "1.R-_2") (pintype "passive"))
      (node (ref "R1") (pin "2") (pinfunction "2_2") (pintype "passive"))
    )
    (net (code "27") (name "Net-(LED1-2.G-)") (class "Default")
      (node (ref "LED1") (pin "3") (pinfunction "2.G-_3") (pintype "passive"))
      (node (ref "R2") (pin "2") (pinfunction "2_2") (pintype "passive"))
    )
    (net (code "28") (name "Net-(LED1-4.B-)") (class "Default")
      (node (ref "LED1") (pin "1") (pinfunction "4.B-_1") (pintype "passive"))
      (node (ref "R3") (pin "2") (pinfunction "2_2") (pintype "passive"))
    )
    (net (code "29") (name "Net-(LED2-PadA)") (class "Default")
      (node (ref "LED2") (pin "A") (pinfunction "A_A") (pintype "passive"))
      (node (ref "R14") (pin "2") (pinfunction "2_2") (pintype "passive"))
    )
    (net (code "30") (name "Net-(LED3-PadA)") (class "Default")
      (node (ref "LED3") (pin "A") (pinfunction "A_A") (pintype "passive"))
      (node (ref "R15") (pin "2") (pinfunction "2_2") (pintype "passive"))
    )
    (net (code "31") (name "Net-(U2-(1)3V3)") (class "Default")
      (node (ref "D5") (pin "A") (pinfunction "A_A") (pintype "passive"))
      (node (ref "U2") (pin "1.3V3") (pinfunction "(1)3V3_1.3V3") (pintype "bidirectional"))
    )
    (net (code "32") (name "Net-(U7-(1)3V3)") (class "Default")
      (node (ref "D4") (pin "A") (pinfunction "A_A") (pintype "passive"))
      (node (ref "U7") (pin "1.3V3") (pinfunction "(1)3V3_1.3V3") (pintype "bidirectional"))
    )
    (net (code "33") (name "PB0") (class "Default")
      (node (ref "J2") (pin "9") (pinfunction "5.ADC5_9") (pintype "bidirectional"))
      (node (ref "U6") (pin "12") (pinfunction "PB0_12") (pintype "bidirectional"))
    )
    (net (code "34") (name "PB1") (class "Default")
      (node (ref "J2") (pin "10") (pinfunction "5.ADC6_10") (pintype "bidirectional"))
      (node (ref "U6") (pin "13") (pinfunction "PB1_13") (pintype "bidirectional"))
    )
    (net (code "35") (name "PB2") (class "Default")
      (node (ref "J2") (pin "11") (pinfunction "5.ADC7_11") (pintype "bidirectional"))
      (node (ref "U6") (pin "14") (pinfunction "PB2_14") (pintype "bidirectional"))
    )
    (net (code "36") (name "PC0") (class "Default")
      (node (ref "J8") (pin "3") (pinfunction "3.ADC0_3") (pintype "bidirectional"))
      (node (ref "U6") (pin "23") (pinfunction "PC0_23") (pintype "bidirectional"))
    )
    (net (code "37") (name "PC1") (class "Default")
      (node (ref "J8") (pin "4") (pinfunction "4.ADC1_4") (pintype "bidirectional"))
      (node (ref "U6") (pin "24") (pinfunction "PC1_24") (pintype "bidirectional"))
    )
    (net (code "38") (name "PC2") (class "Default")
      (node (ref "J8") (pin "6") (pinfunction "5.ADC2_6") (pintype "bidirectional"))
      (node (ref "U6") (pin "25") (pinfunction "PC2_25") (pintype "bidirectional"))
    )
    (net (code "39") (name "PC3") (class "Default")
      (node (ref "J8") (pin "5") (pinfunction "5.ADC1_5") (pintype "bidirectional"))
      (node (ref "U6") (pin "26") (pinfunction "PC3_26") (pintype "bidirectional"))
    )
    (net (code "40") (name "PD2") (class "Default")
      (node (ref "J2") (pin "3") (pinfunction "3.ADC0_3") (pintype "bidirectional"))
      (node (ref "U6") (pin "32") (pinfunction "PD2_32") (pintype "bidirectional"))
    )
    (net (code "41") (name "PD3") (class "Default")
      (node (ref "J2") (pin "4") (pinfunction "4.ADC1_4") (pintype "bidirectional"))
      (node (ref "U6") (pin "1") (pinfunction "PD3_1") (pintype "bidirectional"))
    )
    (net (code "42") (name "PD4") (class "Default")
      (node (ref "J2") (pin "6") (pinfunction "5.ADC2_6") (pintype "bidirectional"))
      (node (ref "R17") (pin "1") (pinfunction "1_1") (pintype "passive"))
      (node (ref "U6") (pin "2") (pinfunction "PD4_2") (pintype "bidirectional"))
    )
    (net (code "43") (name "PD5") (class "Default")
      (node (ref "J2") (pin "5") (pinfunction "5.ADC1_5") (pintype "bidirectional"))
      (node (ref "U6") (pin "9") (pinfunction "PD5_9") (pintype "bidirectional"))
    )
    (net (code "44") (name "PD6") (class "Default")
      (node (ref "J2") (pin "7") (pinfunction "5.ADC3_7") (pintype "bidirectional"))
      (node (ref "U6") (pin "10") (pinfunction "PD6_10") (pintype "bidirectional"))
    )
    (net (code "45") (name "PD7") (class "Default")
      (node (ref "J2") (pin "8") (pinfunction "5.ADC4_8") (pintype "bidirectional"))
      (node (ref "U6") (pin "11") (pinfunction "PD7_11") (pintype "bidirectional"))
    )
    (net (code "46") (name "RA2") (class "Default")
      (node (ref "R3") (pin "1") (pinfunction "1_1") (pintype "passive"))
      (node (ref "U3") (pin "17") (pinfunction "17.RA2_17") (pintype "bidirectional"))
      (node (ref "U5") (pin "17.L") (pinfunction "17_17.L") (pintype "bidirectional"))
      (node (ref "U5") (pin "17.R") (pinfunction "17_17.R") (pintype "bidirectional"))
    )
    (net (code "47") (name "RA4") (class "Default")
      (node (ref "U1") (pin "1") (pinfunction "1_1") (pintype "bidirectional"))
      (node (ref "U3") (pin "3") (pinfunction "3.RA4_3") (pintype "bidirectional"))
      (node (ref "U5") (pin "3.L") (pinfunction "3_3.L") (pintype "bidirectional"))
      (node (ref "U5") (pin "3.R") (pinfunction "3_3.R") (pintype "bidirectional"))
    )
    (net (code "48") (name "RA5") (class "Default")
      (node (ref "R2") (pin "1") (pinfunction "1_1") (pintype "passive"))
      (node (ref "U3") (pin "2") (pinfunction "2.RA5_2") (pintype "bidirectional"))
      (node (ref "U5") (pin "2.L") (pinfunction "2_2.L") (pintype "bidirectional"))
      (node (ref "U5") (pin "2.R") (pinfunction "2_2.R") (pintype "bidirectional"))
    )
    (net (code "49") (name "RB5") (class "Default")
      (node (ref "J5") (pin "5") (pinfunction "5.ADC2_5") (pintype "bidirectional"))
      (node (ref "U3") (pin "12") (pinfunction "12.RB5_12") (pintype "bidirectional"))
      (node (ref "U5") (pin "12.L") (pinfunction "12_12.L") (pintype "bidirectional"))
      (node (ref "U5") (pin "12.R") (pinfunction "12_12.R") (pintype "bidirectional"))
    )
    (net (code "50") (name "RB7") (class "Default")
      (node (ref "R12") (pin "1") (pinfunction "1_1") (pintype "passive"))
      (node (ref "U3") (pin "10") (pinfunction "10.RB7_10") (pintype "bidirectional"))
      (node (ref "U5") (pin "10.L") (pinfunction "10_10.L") (pintype "bidirectional"))
      (node (ref "U5") (pin "10.R") (pinfunction "10_10.R") (pintype "bidirectional"))
    )
    (net (code "51") (name "RC0") (class "Default")
      (node (ref "U1") (pin "4") (pinfunction "4_4") (pintype "bidirectional"))
      (node (ref "U3") (pin "16") (pinfunction "16.RC0_16") (pintype "bidirectional"))
      (node (ref "U5") (pin "16.L") (pinfunction "16_16.L") (pintype "bidirectional"))
      (node (ref "U5") (pin "16.R") (pinfunction "16_16.R") (pintype "bidirectional"))
    )
    (net (code "52") (name "RC1") (class "Default")
      (node (ref "U1") (pin "3") (pinfunction "3_3") (pintype "bidirectional"))
      (node (ref "U3") (pin "15") (pinfunction "15.RC1_15") (pintype "bidirectional"))
      (node (ref "U5") (pin "15.L") (pinfunction "15_15.L") (pintype "bidirectional"))
      (node (ref "U5") (pin "15.R") (pinfunction "15_15.R") (pintype "bidirectional"))
    )
    (net (code "53") (name "RC2") (class "Default")
      (node (ref "J5") (pin "3") (pinfunction "3.ADC0_3") (pintype "bidirectional"))
      (node (ref "U3") (pin "14") (pinfunction "14.RC2_14") (pintype "bidirectional"))
      (node (ref "U5") (pin "14.L") (pinfunction "14_14.L") (pintype "bidirectional"))
      (node (ref "U5") (pin "14.R") (pinfunction "14_14.R") (pintype "bidirectional"))
    )
    (net (code "54") (name "RC3") (class "Default")
      (node (ref "J5") (pin "4") (pinfunction "4.ADC1_4") (pintype "bidirectional"))
      (node (ref "U3") (pin "7") (pinfunction "7.RC3_7") (pintype "bidirectional"))
      (node (ref "U5") (pin "7.L") (pinfunction "7_7.L") (pintype "bidirectional"))
      (node (ref "U5") (pin "7.R") (pinfunction "7_7.R") (pintype "bidirectional"))
    )
    (net (code "55") (name "RC4") (class "Default")
      (node (ref "U2") (pin "3.RXI") (pinfunction "(3)MCU.TX_3.RXI") (pintype "bidirectional"))
      (node (ref "U3") (pin "6") (pinfunction "6.RC4_6") (pintype "bidirectional"))
      (node (ref "U5") (pin "6.L") (pinfunction "6_6.L") (pintype "bidirectional"))
      (node (ref "U5") (pin "6.R") (pinfunction "6_6.R") (pintype "bidirectional"))
    )
    (net (code "56") (name "RC5") (class "Default")
      (node (ref "U2") (pin "4.RDO") (pinfunction "(4)MCU.RX_4.RDO") (pintype "bidirectional"))
      (node (ref "U3") (pin "5") (pinfunction "5.RC5_5") (pintype "bidirectional"))
      (node (ref "U5") (pin "5.L") (pinfunction "5_5.L") (pintype "bidirectional"))
      (node (ref "U5") (pin "5.R") (pinfunction "5_5.R") (pintype "bidirectional"))
    )
    (net (code "57") (name "RC6") (class "Default")
      (node (ref "R1") (pin "1") (pinfunction "1_1") (pintype "passive"))
      (node (ref "U3") (pin "8") (pinfunction "8.RC6_8") (pintype "bidirectional"))
      (node (ref "U5") (pin "8.L") (pinfunction "8_8.L") (pintype "bidirectional"))
      (node (ref "U5") (pin "8.R") (pinfunction "8_8.R") (pintype "bidirectional"))
    )
    (net (code "58") (name "RC7") (class "Default")
      (node (ref "U1") (pin "2") (pinfunction "2_2") (pintype "bidirectional"))
      (node (ref "U3") (pin "9") (pinfunction "9.RC7_9") (pintype "bidirectional"))
      (node (ref "U5") (pin "9.L") (pinfunction "9_9.L") (pintype "bidirectional"))
      (node (ref "U5") (pin "9.R") (pinfunction "9_9.R") (pintype "bidirectional"))
    )
    (net (code "59") (name "SCL") (class "Default")
      (node (ref "R6") (pin "2") (pinfunction "2_2") (pintype "passive"))
      (node (ref "U$3") (pin "3.SCL") (pinfunction "3.SCL_3.SCL") (pintype "bidirectional"))
      (node (ref "U3") (pin "11") (pinfunction "11.RB6_11") (pintype "bidirectional"))
      (node (ref "U4") (pin "4") (pinfunction "4.SCL_4") (pintype "bidirectional"))
      (node (ref "U5") (pin "11.L") (pinfunction "11_11.L") (pintype "bidirectional"))
      (node (ref "U5") (pin "11.R") (pinfunction "11_11.R") (pintype "bidirectional"))
      (node (ref "U6") (pin "28") (pinfunction "PC5_28") (pintype "bidirectional"))
    )
    (net (code "60") (name "SDA") (class "Default")
      (node (ref "R5") (pin "2") (pinfunction "2_2") (pintype "passive"))
      (node (ref "U$3") (pin "4.SDA") (pinfunction "4.SDA_4.SDA") (pintype "bidirectional"))
      (node (ref "U3") (pin "13") (pinfunction "13.RB4_13") (pintype "bidirectional"))
      (node (ref "U4") (pin "3") (pinfunction "3.SDA_3") (pintype "bidirectional"))
      (node (ref "U5") (pin "13.L") (pinfunction "13_13.L") (pintype "bidirectional"))
      (node (ref "U5") (pin "13.R") (pinfunction "13_13.R") (pintype "bidirectional"))
      (node (ref "U6") (pin "27") (pinfunction "PC4_27") (pintype "bidirectional"))
    )
    (net (code "61") (name "VDD") (class "Default")
      (node (ref "C1") (pin "1") (pinfunction "+_1") (pintype "passive"))
      (node (ref "C12") (pin "1") (pinfunction "+_1") (pintype "passive"))
      (node (ref "C13") (pin "1") (pinfunction "+_1") (pintype "passive"))
      (node (ref "C2") (pin "1") (pinfunction "+_1") (pintype "passive"))
      (node (ref "C20") (pin "1") (pinfunction "+_1") (pintype "passive"))
      (node (ref "C21") (pin "1") (pinfunction "+_1") (pintype "passive"))
      (node (ref "C3") (pin "1") (pinfunction "+_1") (pintype "passive"))
      (node (ref "C6") (pin "1") (pinfunction "+_1") (pintype "passive"))
      (node (ref "J1") (pin "2") (pinfunction "2_2") (pintype "bidirectional"))
      (node (ref "J2") (pin "2") (pinfunction "2.VDD_2") (pintype "bidirectional"))
      (node (ref "J3") (pin "2") (pinfunction "2_2") (pintype "bidirectional"))
      (node (ref "J4") (pin "2") (pinfunction "2.VDD(PWR)_2") (pintype "bidirectional"))
      (node (ref "J5") (pin "2") (pinfunction "2.VDD_2") (pintype "bidirectional"))
      (node (ref "J8") (pin "2") (pinfunction "2.VDD_2") (pintype "bidirectional"))
      (node (ref "LED1") (pin "4") (pinfunction "3.+_4") (pintype "passive"))
      (node (ref "R10") (pin "1") (pinfunction "1_1") (pintype "passive"))
      (node (ref "R11") (pin "1") (pinfunction "1_1") (pintype "passive"))
      (node (ref "R15") (pin "1") (pinfunction "1_1") (pintype "passive"))
      (node (ref "R16") (pin "1") (pinfunction "1_1") (pintype "passive"))
      (node (ref "R4") (pin "1") (pinfunction "1_1") (pintype "passive"))
      (node (ref "R5") (pin "1") (pinfunction "1_1") (pintype "passive"))
      (node (ref "R6") (pin "1") (pinfunction "1_1") (pintype "passive"))
      (node (ref "R8") (pin "1") (pinfunction "1_1") (pintype "passive"))
      (node (ref "U$3") (pin "2.VDD") (pinfunction "1.VDD_2.VDD") (pintype "bidirectional"))
      (node (ref "U3") (pin "1") (pinfunction "1.VDD_1") (pintype "bidirectional"))
      (node (ref "U4") (pin "2") (pinfunction "2.VDD_2") (pintype "bidirectional"))
      (node (ref "U5") (pin "1.L") (pinfunction "1_1.L") (pintype "bidirectional"))
      (node (ref "U5") (pin "1.R") (pinfunction "1_1.R") (pintype "bidirectional"))
      (node (ref "U6") (pin "4") (pinfunction "VCC_2_4") (pintype "power_in"))
      (node (ref "U6") (pin "6") (pinfunction "VCC_6") (pintype "power_in"))
    )
    (net (code "62") (name "XTAL1") (class "Default")
      (node (ref "C7") (pin "2") (pinfunction "+_2") (pintype "passive"))
      (node (ref "U6") (pin "7") (pinfunction "PB6_7") (pintype "bidirectional"))
      (node (ref "XTAL1") (pin "3") (pinfunction "2_3") (pintype "bidirectional"))
    )
    (net (code "63") (name "XTAL2") (class "Default")
      (node (ref "C8") (pin "2") (pinfunction "+_2") (pintype "passive"))
      (node (ref "U6") (pin "8") (pinfunction "PB7_8") (pintype "bidirectional"))
      (node (ref "XTAL1") (pin "1") (pinfunction "1_1") (pintype "bidirectional"))
    )
    (net (code "64") (name "unconnected-(J2-5.ADC8-Pad12)") (class "Default")
      (node (ref "J2") (pin "12") (pinfunction "5.ADC8_12") (pintype "bidirectional"))
    )
    (net (code "65") (name "unconnected-(J4-6.PGM-Pad6)") (class "Default")
      (node (ref "J4") (pin "6") (pinfunction "6.PGM_6") (pintype "bidirectional"))
    )
    (net (code "66") (name "unconnected-(J7-PadRING_SW)") (class "Default")
      (node (ref "J7") (pin "RING_SW") (pinfunction "RING_SW_RING_SW") (pintype "bidirectional"))
    )
    (net (code "67") (name "unconnected-(U2-(2)DTR-Pad2.DTR)") (class "Default")
      (node (ref "U2") (pin "2.DTR") (pinfunction "(2)DTR_2.DTR") (pintype "bidirectional"))
    )
  )
)
